# board.net
KiCad netlist of a schematic drawn in EAGLE
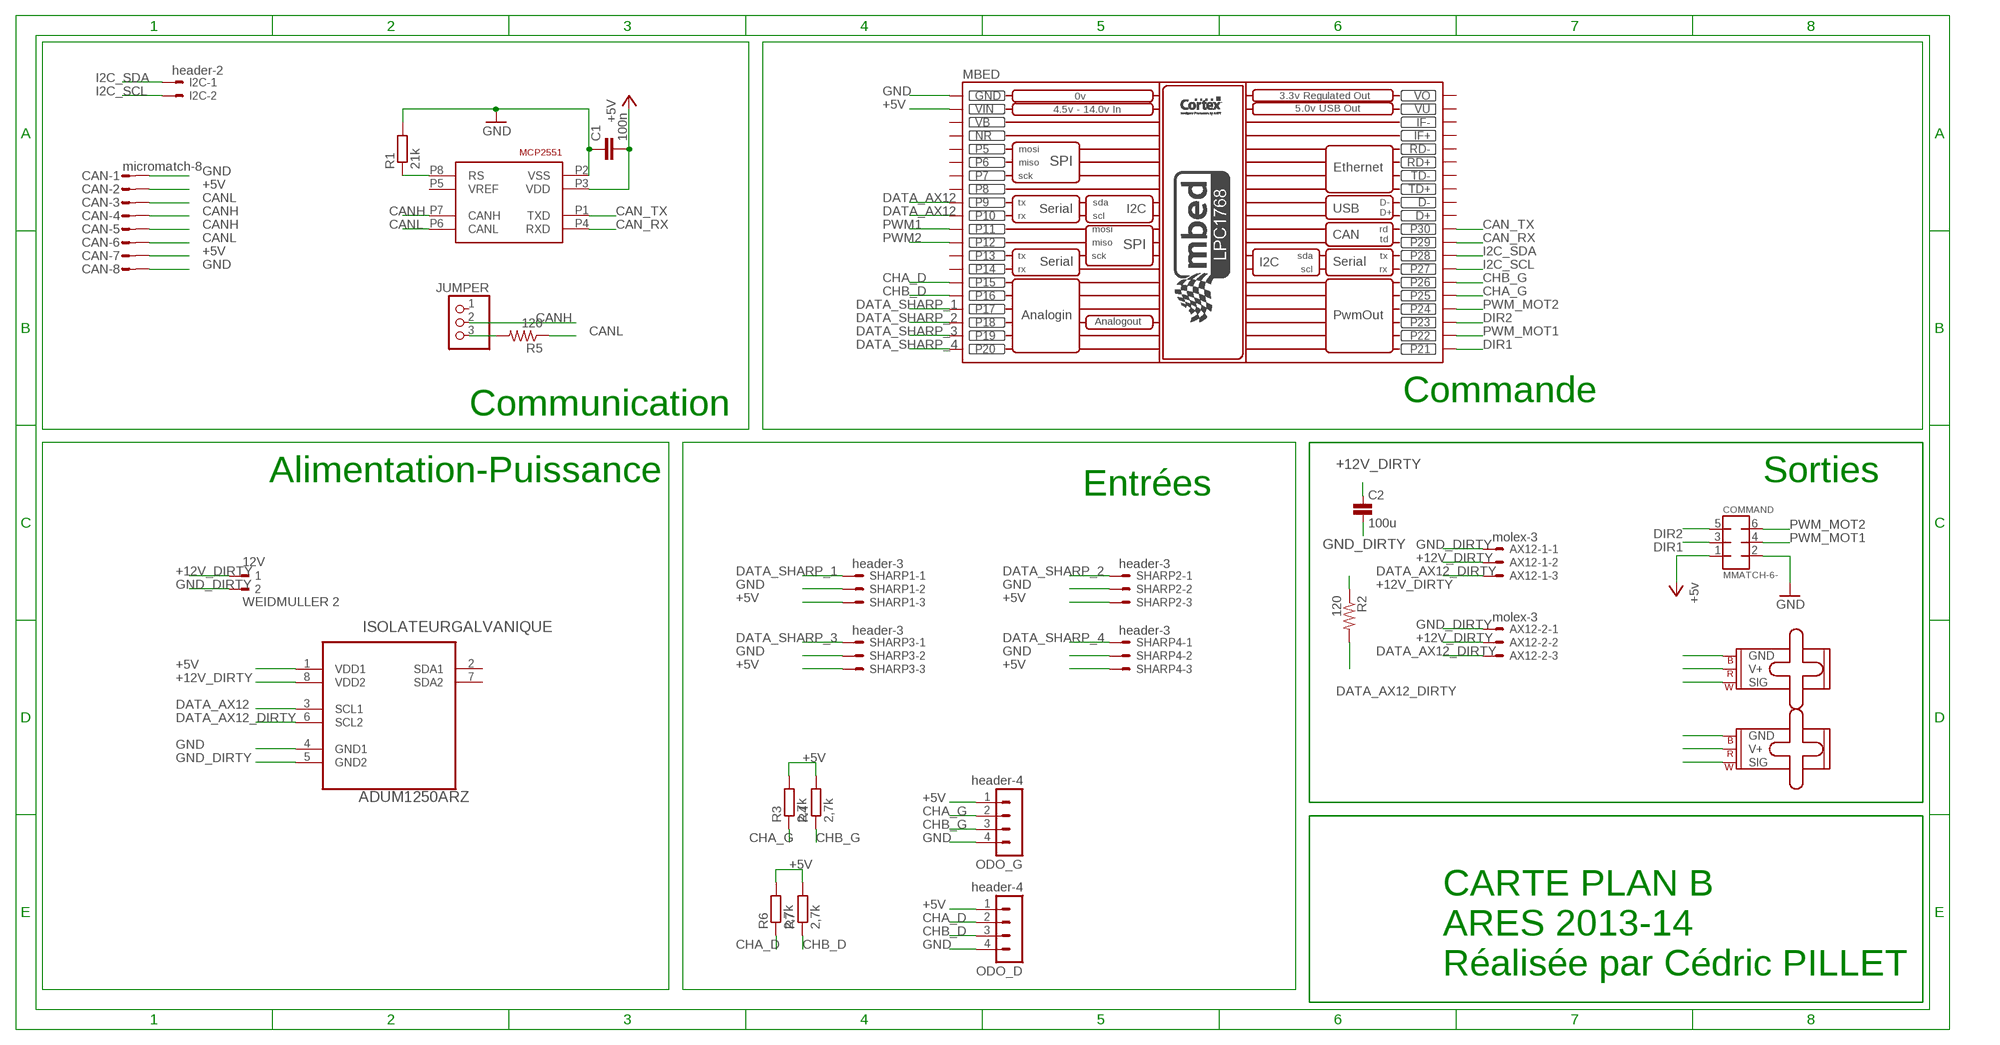
[diagram p0: schematic, sheet 1]

(export (version "E")
  (design (tool "Eeschema 10.0.6"))
  (components
    (comp (ref "12V")
      (value "WEIDMULLER 2")
      (footprint "eagle-import:90G-2")
      (libsource (lib "eagle-import") (part "90G-2"))
    )
    (comp (ref "AX12-1")
      (value "molex-3")
      (footprint "eagle-import:22-23-2031")
      (fields (field (name "MF") "MOLEX") (field (name "MPN") "22-23-2031"))
      (libsource (lib "eagle-import") (part "22-23-2031"))
    )
    (comp (ref "AX12-2")
      (value "molex-3")
      (footprint "eagle-import:22-23-2031")
      (fields (field (name "MF") "MOLEX") (field (name "MPN") "22-23-2031"))
      (libsource (lib "eagle-import") (part "22-23-2031"))
    )
    (comp (ref "C1")
      (value "100n")
      (footprint "eagle-import:C0805")
      (libsource (lib "eagle-import") (part "C-EUC0805"))
    )
    (comp (ref "C2")
      (value "100u")
      (footprint "eagle-import:0805")
      (libsource (lib "eagle-import") (part "C0805"))
    )
    (comp (ref "CAN")
      (value "micromatch-8")
      (footprint "eagle-import:MICROMATCH-8")
      (fields (field (name "MF") "FARNELL") (field (name "MPN") "7-215464-8"))
      (libsource (lib "eagle-import") (part "MICROMATCH-8"))
    )
    (comp (ref "COMMAND")
      (value "MMATCH-6-")
      (footprint "eagle-import:AMP-215079-6")
      (libsource (lib "eagle-import") (part "MMATCH-6-"))
    )
    (comp (ref "I2C")
      (value "header-2")
      (footprint "eagle-import:22-23-2021")
      (fields (field (name "MF") "MOLEX") (field (name "MPN") "22-23-2021"))
      (libsource (lib "eagle-import") (part "22-23-2021"))
    )
    (comp (ref "ISOLATEURGALVANIQUE")
      (value "ADUM1250ARZ")
      (footprint "eagle-import:SOIC127P600X175-8N")
      (libsource (lib "eagle-import") (part "ADUM1250ARZ"))
    )
    (comp (ref "JUMPER")
      (value "PINHD-1X3")
      (footprint "eagle-import:1X03")
      (libsource (lib "eagle-import") (part "PINHD-1X3"))
    )
    (comp (ref "M1")
      (value "SMALL_SERVO")
      (footprint "eagle-import:1X03")
      (libsource (lib "eagle-import") (part "SMALL_SERVO"))
    )
    (comp (ref "M2")
      (value "SMALL_SERVO")
      (footprint "eagle-import:1X03")
      (libsource (lib "eagle-import") (part "SMALL_SERVO"))
    )
    (comp (ref "MBED")
      (value "MBED_NXP_LPC1768")
      (footprint "eagle-import:MBED-KIT")
      (libsource (lib "eagle-import") (part "MBED_NXP_LPC1768"))
    )
    (comp (ref "ODO_D")
      (value "header-4")
      (footprint "eagle-import:MA04-1")
      (libsource (lib "eagle-import") (part "MA04-1"))
    )
    (comp (ref "ODO_G")
      (value "header-4")
      (footprint "eagle-import:MA04-1")
      (libsource (lib "eagle-import") (part "MA04-1"))
    )
    (comp (ref "R1")
      (value "21k")
      (footprint "eagle-import:R0805")
      (libsource (lib "eagle-import") (part "R-EU_R0805"))
    )
    (comp (ref "R2")
      (value "120")
      (footprint "eagle-import:M0805")
      (libsource (lib "eagle-import") (part "R-US_M0805"))
    )
    (comp (ref "R3")
      (value "2,7k")
      (footprint "eagle-import:R0805")
      (libsource (lib "eagle-import") (part "R-EU_R0805"))
    )
    (comp (ref "R4")
      (value "2,7k")
      (footprint "eagle-import:R0805")
      (libsource (lib "eagle-import") (part "R-EU_R0805"))
    )
    (comp (ref "R5")
      (value "120")
      (footprint "eagle-import:M0805")
      (libsource (lib "eagle-import") (part "R-US_M0805"))
    )
    (comp (ref "R6")
      (value "2,7k")
      (footprint "eagle-import:R0805")
      (libsource (lib "eagle-import") (part "R-EU_R0805"))
    )
    (comp (ref "R7")
      (value "2,7k")
      (footprint "eagle-import:R0805")
      (libsource (lib "eagle-import") (part "R-EU_R0805"))
    )
    (comp (ref "SHARP1")
      (value "header-3")
      (footprint "eagle-import:22-23-2031")
      (fields (field (name "MF") "MOLEX") (field (name "MPN") "22-23-2031"))
      (libsource (lib "eagle-import") (part "22-23-2031"))
    )
    (comp (ref "SHARP2")
      (value "header-3")
      (footprint "eagle-import:22-23-2031")
      (fields (field (name "MF") "MOLEX") (field (name "MPN") "22-23-2031"))
      (libsource (lib "eagle-import") (part "22-23-2031"))
    )
    (comp (ref "SHARP3")
      (value "header-3")
      (footprint "eagle-import:22-23-2031")
      (fields (field (name "MF") "MOLEX") (field (name "MPN") "22-23-2031"))
      (libsource (lib "eagle-import") (part "22-23-2031"))
    )
    (comp (ref "SHARP4")
      (value "header-3")
      (footprint "eagle-import:22-23-2031")
      (fields (field (name "MF") "MOLEX") (field (name "MPN") "22-23-2031"))
      (libsource (lib "eagle-import") (part "22-23-2031"))
    )
    (comp (ref "TRANSCEIVER")
      (value "MCP2551")
      (footprint "eagle-import:SOIC_8")
      (libsource (lib "eagle-import") (part "MCP2551"))
    )
  )
  (nets
    (net (code "1") (name "+5V") (class "Default")
      (node (ref "C1") (pin "2") (pinfunction "2_2") (pintype "passive"))
      (node (ref "CAN") (pin "2") (pinfunction "S_2") (pintype "passive"))
      (node (ref "CAN") (pin "7") (pinfunction "S_7") (pintype "passive"))
      (node (ref "COMMAND") (pin "1") (pinfunction "3_1") (pintype "bidirectional"))
      (node (ref "ISOLATEURGALVANIQUE") (pin "1") (pinfunction "VDD1_1") (pintype "power_in"))
      (node (ref "M1") (pin "2") (pinfunction "V+_2") (pintype "bidirectional"))
      (node (ref "M2") (pin "2") (pinfunction "V+_2") (pintype "bidirectional"))
      (node (ref "MBED") (pin "VIN") (pinfunction "VIN_VIN") (pintype "power_in"))
      (node (ref "ODO_D") (pin "1") (pinfunction "1_1") (pintype "passive"))
      (node (ref "ODO_G") (pin "1") (pinfunction "1_1") (pintype "passive"))
      (node (ref "R3") (pin "2") (pinfunction "2_2") (pintype "passive"))
      (node (ref "R4") (pin "2") (pinfunction "2_2") (pintype "passive"))
      (node (ref "R6") (pin "2") (pinfunction "2_2") (pintype "passive"))
      (node (ref "R7") (pin "2") (pinfunction "2_2") (pintype "passive"))
      (node (ref "SHARP1") (pin "3") (pinfunction "S_3") (pintype "passive"))
      (node (ref "SHARP2") (pin "3") (pinfunction "S_3") (pintype "passive"))
      (node (ref "SHARP3") (pin "3") (pinfunction "S_3") (pintype "passive"))
      (node (ref "SHARP4") (pin "3") (pinfunction "S_3") (pintype "passive"))
      (node (ref "TRANSCEIVER") (pin "P3") (pinfunction "VDD_P3") (pintype "bidirectional"))
    )
    (net (code "2") (name "/+12V_DIRTY") (class "Default")
      (node (ref "12V") (pin "1") (pinfunction "1_1") (pintype "passive"))
      (node (ref "AX12-1") (pin "2") (pinfunction "S_2") (pintype "passive"))
      (node (ref "AX12-2") (pin "2") (pinfunction "S_2") (pintype "passive"))
      (node (ref "C2") (pin "1") (pinfunction "P$1_1") (pintype "passive"))
      (node (ref "ISOLATEURGALVANIQUE") (pin "8") (pinfunction "VDD2_8") (pintype "power_in"))
      (node (ref "R2") (pin "1") (pinfunction "1_1") (pintype "passive"))
    )
    (net (code "3") (name "/CANH") (class "Default")
      (node (ref "CAN") (pin "4") (pinfunction "S_4") (pintype "passive"))
      (node (ref "CAN") (pin "5") (pinfunction "S_5") (pintype "passive"))
      (node (ref "JUMPER") (pin "2") (pinfunction "2_2") (pintype "passive"))
      (node (ref "TRANSCEIVER") (pin "P7") (pinfunction "CANH_P7") (pintype "bidirectional"))
    )
    (net (code "4") (name "/CANL") (class "Default")
      (node (ref "CAN") (pin "3") (pinfunction "S_3") (pintype "passive"))
      (node (ref "CAN") (pin "6") (pinfunction "S_6") (pintype "passive"))
      (node (ref "R5") (pin "1") (pinfunction "1_1") (pintype "passive"))
      (node (ref "TRANSCEIVER") (pin "P6") (pinfunction "CANL_P6") (pintype "bidirectional"))
    )
    (net (code "5") (name "/CAN_RX") (class "Default")
      (node (ref "MBED") (pin "P$29") (pinfunction "P29_P$29") (pintype "bidirectional"))
      (node (ref "TRANSCEIVER") (pin "P4") (pinfunction "RXD_P4") (pintype "bidirectional"))
    )
    (net (code "6") (name "/CAN_TX") (class "Default")
      (node (ref "MBED") (pin "P$30") (pinfunction "P30_P$30") (pintype "bidirectional"))
      (node (ref "TRANSCEIVER") (pin "P1") (pinfunction "TXD_P1") (pintype "bidirectional"))
    )
    (net (code "7") (name "/CHA_D") (class "Default")
      (node (ref "MBED") (pin "P$15") (pinfunction "P15_P$15") (pintype "bidirectional"))
      (node (ref "ODO_D") (pin "2") (pinfunction "2_2") (pintype "passive"))
      (node (ref "R6") (pin "1") (pinfunction "1_1") (pintype "passive"))
    )
    (net (code "8") (name "/CHA_G") (class "Default")
      (node (ref "MBED") (pin "P$25") (pinfunction "P25_P$25") (pintype "bidirectional"))
      (node (ref "ODO_G") (pin "2") (pinfunction "2_2") (pintype "passive"))
      (node (ref "R3") (pin "1") (pinfunction "1_1") (pintype "passive"))
    )
    (net (code "9") (name "/CHB_D") (class "Default")
      (node (ref "MBED") (pin "P$16") (pinfunction "P16_P$16") (pintype "bidirectional"))
      (node (ref "ODO_D") (pin "3") (pinfunction "3_3") (pintype "passive"))
      (node (ref "R7") (pin "1") (pinfunction "1_1") (pintype "passive"))
    )
    (net (code "10") (name "/CHB_G") (class "Default")
      (node (ref "MBED") (pin "P$26") (pinfunction "P26_P$26") (pintype "bidirectional"))
      (node (ref "ODO_G") (pin "3") (pinfunction "3_3") (pintype "passive"))
      (node (ref "R4") (pin "1") (pinfunction "1_1") (pintype "passive"))
    )
    (net (code "11") (name "/DATA_AX12") (class "Default")
      (node (ref "ISOLATEURGALVANIQUE") (pin "3") (pinfunction "SCL1_3") (pintype "input"))
      (node (ref "MBED") (pin "P$10") (pinfunction "P10_P$10") (pintype "bidirectional"))
      (node (ref "MBED") (pin "P$9") (pinfunction "P9_P$9") (pintype "bidirectional"))
    )
    (net (code "12") (name "/DATA_AX12_DIRTY") (class "Default")
      (node (ref "AX12-1") (pin "3") (pinfunction "S_3") (pintype "passive"))
      (node (ref "AX12-2") (pin "3") (pinfunction "S_3") (pintype "passive"))
      (node (ref "ISOLATEURGALVANIQUE") (pin "6") (pinfunction "SCL2_6") (pintype "input"))
      (node (ref "R2") (pin "2") (pinfunction "2_2") (pintype "passive"))
    )
    (net (code "13") (name "/DATA_SHARP_1") (class "Default")
      (node (ref "MBED") (pin "P$17") (pinfunction "P17_P$17") (pintype "bidirectional"))
      (node (ref "SHARP1") (pin "1") (pinfunction "S_1") (pintype "passive"))
    )
    (net (code "14") (name "/DATA_SHARP_2") (class "Default")
      (node (ref "MBED") (pin "P$18") (pinfunction "P18_P$18") (pintype "bidirectional"))
      (node (ref "SHARP2") (pin "1") (pinfunction "S_1") (pintype "passive"))
    )
    (net (code "15") (name "/DATA_SHARP_3") (class "Default")
      (node (ref "MBED") (pin "P$19") (pinfunction "P19_P$19") (pintype "bidirectional"))
      (node (ref "SHARP3") (pin "1") (pinfunction "S_1") (pintype "passive"))
    )
    (net (code "16") (name "/DATA_SHARP_4") (class "Default")
      (node (ref "MBED") (pin "P$20") (pinfunction "P20_P$20") (pintype "bidirectional"))
      (node (ref "SHARP4") (pin "1") (pinfunction "S_1") (pintype "passive"))
    )
    (net (code "17") (name "/DIR1") (class "Default")
      (node (ref "COMMAND") (pin "3") (pinfunction "5_3") (pintype "bidirectional"))
      (node (ref "MBED") (pin "P$21") (pinfunction "P21_P$21") (pintype "bidirectional"))
    )
    (net (code "18") (name "/DIR2") (class "Default")
      (node (ref "COMMAND") (pin "5") (pinfunction "7_5") (pintype "bidirectional"))
      (node (ref "MBED") (pin "P$23") (pinfunction "P23_P$23") (pintype "bidirectional"))
    )
    (net (code "19") (name "/GND_DIRTY") (class "Default")
      (node (ref "12V") (pin "2") (pinfunction "2_2") (pintype "passive"))
      (node (ref "AX12-1") (pin "1") (pinfunction "S_1") (pintype "passive"))
      (node (ref "AX12-2") (pin "1") (pinfunction "S_1") (pintype "passive"))
      (node (ref "C2") (pin "2") (pinfunction "P$2_2") (pintype "passive"))
      (node (ref "ISOLATEURGALVANIQUE") (pin "5") (pinfunction "GND2_5") (pintype "passive"))
    )
    (net (code "20") (name "/I2C_SCL") (class "Default")
      (node (ref "I2C") (pin "2") (pinfunction "S_2") (pintype "passive"))
      (node (ref "MBED") (pin "P$27") (pinfunction "P27_P$27") (pintype "bidirectional"))
    )
    (net (code "21") (name "/I2C_SDA") (class "Default")
      (node (ref "I2C") (pin "1") (pinfunction "S_1") (pintype "passive"))
      (node (ref "MBED") (pin "P$28") (pinfunction "P28_P$28") (pintype "bidirectional"))
    )
    (net (code "22") (name "/NR") (class "Default")
      (node (ref "MBED") (pin "NR") (pinfunction "NR_NR") (pintype "power_in"))
    )
    (net (code "23") (name "/PWM1") (class "Default")
      (node (ref "M1") (pin "1") (pinfunction "SIG_1") (pintype "bidirectional"))
      (node (ref "MBED") (pin "P$11") (pinfunction "P11_P$11") (pintype "bidirectional"))
    )
    (net (code "24") (name "/PWM2") (class "Default")
      (node (ref "M2") (pin "1") (pinfunction "SIG_1") (pintype "bidirectional"))
      (node (ref "MBED") (pin "P$12") (pinfunction "P12_P$12") (pintype "bidirectional"))
    )
    (net (code "25") (name "/PWM_MOT1") (class "Default")
      (node (ref "COMMAND") (pin "4") (pinfunction "6_4") (pintype "bidirectional"))
      (node (ref "MBED") (pin "P$22") (pinfunction "P22_P$22") (pintype "bidirectional"))
    )
    (net (code "26") (name "/PWM_MOT2") (class "Default")
      (node (ref "COMMAND") (pin "6") (pinfunction "8_6") (pintype "bidirectional"))
      (node (ref "MBED") (pin "P$24") (pinfunction "P24_P$24") (pintype "bidirectional"))
    )
    (net (code "27") (name "/VB") (class "Default")
      (node (ref "MBED") (pin "VB") (pinfunction "VB_VB") (pintype "power_in"))
    )
    (net (code "28") (name "/VO") (class "Default")
      (node (ref "MBED") (pin "VOUT") (pinfunction "VO_VOUT") (pintype "power_in"))
    )
    (net (code "29") (name "/VU") (class "Default")
      (node (ref "MBED") (pin "VU") (pinfunction "VU_VU") (pintype "power_in"))
    )
    (net (code "30") (name "GND") (class "Default")
      (node (ref "C1") (pin "1") (pinfunction "1_1") (pintype "passive"))
      (node (ref "CAN") (pin "1") (pinfunction "S_1") (pintype "passive"))
      (node (ref "CAN") (pin "8") (pinfunction "S_8") (pintype "passive"))
      (node (ref "COMMAND") (pin "2") (pinfunction "4_2") (pintype "bidirectional"))
      (node (ref "ISOLATEURGALVANIQUE") (pin "4") (pinfunction "GND1_4") (pintype "passive"))
      (node (ref "M1") (pin "3") (pinfunction "GND_3") (pintype "bidirectional"))
      (node (ref "M2") (pin "3") (pinfunction "GND_3") (pintype "bidirectional"))
      (node (ref "MBED") (pin "GND") (pinfunction "GND_GND") (pintype "power_in"))
      (node (ref "ODO_D") (pin "4") (pinfunction "4_4") (pintype "passive"))
      (node (ref "ODO_G") (pin "4") (pinfunction "4_4") (pintype "passive"))
      (node (ref "R1") (pin "2") (pinfunction "2_2") (pintype "passive"))
      (node (ref "SHARP1") (pin "2") (pinfunction "S_2") (pintype "passive"))
      (node (ref "SHARP2") (pin "2") (pinfunction "S_2") (pintype "passive"))
      (node (ref "SHARP3") (pin "2") (pinfunction "S_2") (pintype "passive"))
      (node (ref "SHARP4") (pin "2") (pinfunction "S_2") (pintype "passive"))
      (node (ref "TRANSCEIVER") (pin "P2") (pinfunction "VSS_P2") (pintype "bidirectional"))
    )
    (net (code "31") (name "Net-(JUMPER-Pad3)") (class "Default")
      (node (ref "JUMPER") (pin "3") (pinfunction "3_3") (pintype "passive"))
      (node (ref "R5") (pin "2") (pinfunction "2_2") (pintype "passive"))
    )
    (net (code "32") (name "Net-(TRANSCEIVER-RS)") (class "Default")
      (node (ref "R1") (pin "1") (pinfunction "1_1") (pintype "passive"))
      (node (ref "TRANSCEIVER") (pin "P8") (pinfunction "RS_P8") (pintype "bidirectional"))
    )
    (net (code "33") (name "unconnected-(ISOLATEURGALVANIQUE-SDA1-Pad2)") (class "Default")
      (node (ref "ISOLATEURGALVANIQUE") (pin "2") (pinfunction "SDA1_2") (pintype "bidirectional"))
    )
    (net (code "34") (name "unconnected-(ISOLATEURGALVANIQUE-SDA2-Pad7)") (class "Default")
      (node (ref "ISOLATEURGALVANIQUE") (pin "7") (pinfunction "SDA2_7") (pintype "bidirectional"))
    )
    (net (code "35") (name "unconnected-(JUMPER-Pad1)") (class "Default")
      (node (ref "JUMPER") (pin "1") (pinfunction "1_1") (pintype "passive"))
    )
    (net (code "36") (name "unconnected-(MBED-P5-PadP$5)") (class "Default")
      (node (ref "MBED") (pin "P$5") (pinfunction "P5_P$5") (pintype "bidirectional"))
    )
    (net (code "37") (name "unconnected-(MBED-P6-PadP$6)") (class "Default")
      (node (ref "MBED") (pin "P$6") (pinfunction "P6_P$6") (pintype "bidirectional"))
    )
    (net (code "38") (name "unconnected-(MBED-P7-PadP$7)") (class "Default")
      (node (ref "MBED") (pin "P$7") (pinfunction "P7_P$7") (pintype "bidirectional"))
    )
    (net (code "39") (name "unconnected-(MBED-P8-PadP$8)") (class "Default")
      (node (ref "MBED") (pin "P$8") (pinfunction "P8_P$8") (pintype "bidirectional"))
    )
    (net (code "40") (name "unconnected-(MBED-P13-PadP$13)") (class "Default")
      (node (ref "MBED") (pin "P$13") (pinfunction "P13_P$13") (pintype "bidirectional"))
    )
    (net (code "41") (name "unconnected-(MBED-P14-PadP$14)") (class "Default")
      (node (ref "MBED") (pin "P$14") (pinfunction "P14_P$14") (pintype "bidirectional"))
    )
    (net (code "42") (name "unconnected-(MBED-PadD+)") (class "Default")
      (node (ref "MBED") (pin "D+") (pinfunction "D+_D+") (pintype "bidirectional"))
    )
    (net (code "43") (name "unconnected-(MBED-PadD-)") (class "Default")
      (node (ref "MBED") (pin "D-") (pinfunction "D-_D-") (pintype "bidirectional"))
    )
    (net (code "44") (name "unconnected-(MBED-PadIF+)") (class "Default")
      (node (ref "MBED") (pin "IF+") (pinfunction "IF+_IF+") (pintype "bidirectional"))
    )
    (net (code "45") (name "unconnected-(MBED-PadIF-)") (class "Default")
      (node (ref "MBED") (pin "IF-") (pinfunction "IF-_IF-") (pintype "bidirectional"))
    )
    (net (code "46") (name "unconnected-(MBED-PadRD+)") (class "Default")
      (node (ref "MBED") (pin "RD+") (pinfunction "RD+_RD+") (pintype "bidirectional"))
    )
    (net (code "47") (name "unconnected-(MBED-PadRD-)") (class "Default")
      (node (ref "MBED") (pin "RD-") (pinfunction "RD-_RD-") (pintype "bidirectional"))
    )
    (net (code "48") (name "unconnected-(MBED-PadTD+)") (class "Default")
      (node (ref "MBED") (pin "TD+") (pinfunction "TD+_TD+") (pintype "bidirectional"))
    )
    (net (code "49") (name "unconnected-(MBED-PadTD-)") (class "Default")
      (node (ref "MBED") (pin "TD-") (pinfunction "TD-_TD-") (pintype "bidirectional"))
    )
    (net (code "50") (name "unconnected-(TRANSCEIVER-VREF-PadP5)") (class "Default")
      (node (ref "TRANSCEIVER") (pin "P5") (pinfunction "VREF_P5") (pintype "bidirectional"))
    )
  )
)
